# Adaptor485.net
KiCad netlist of a schematic drawn in EAGLE
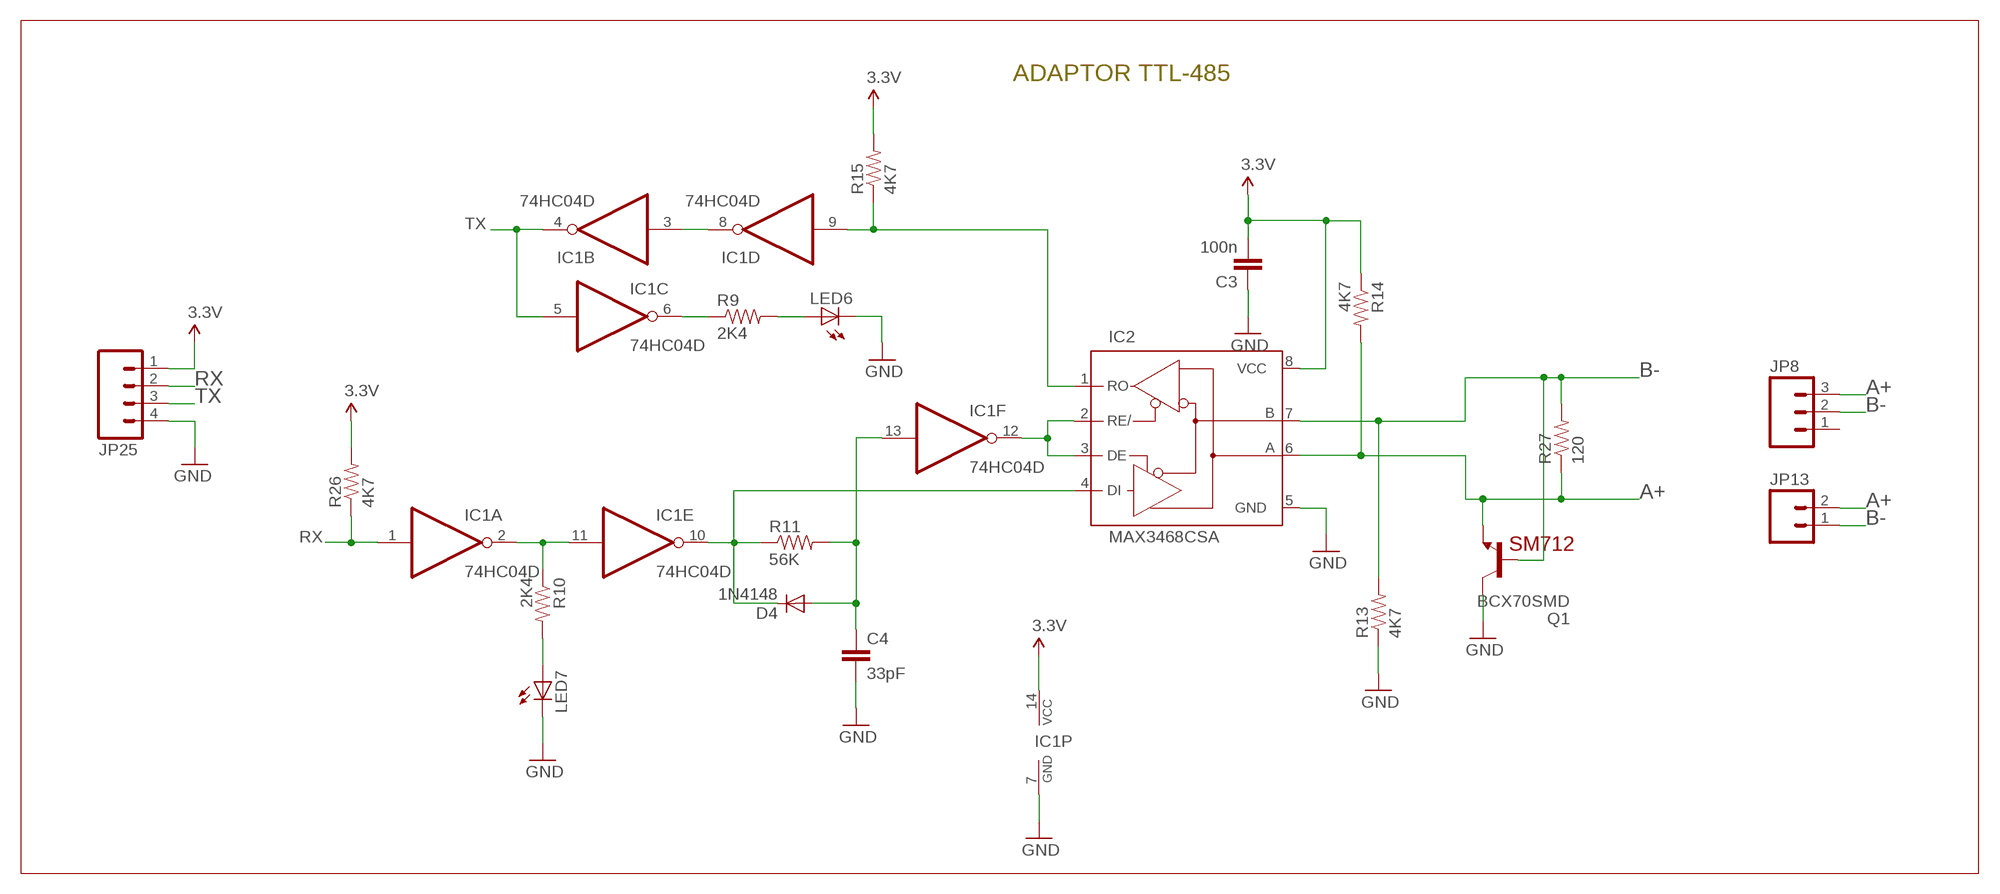
[diagram p0: schematic, sheet 1]

(export (version "E")
  (design (tool "Eeschema 10.0.6"))
  (components
    (comp (ref "C3")
      (value "100n")
      (footprint "eagle-import:0805")
      (libsource (lib "eagle-import") (part "CAP0805"))
    )
    (comp (ref "C4")
      (value "33pF")
      (footprint "eagle-import:0805")
      (libsource (lib "eagle-import") (part "CAP0805"))
    )
    (comp (ref "D4")
      (value "1N4148")
      (footprint "eagle-import:MINIMELF")
      (libsource (lib "eagle-import") (part "DIODE-MINIMELF"))
    )
    (comp (ref "IC1")
      (value "74HC04D")
      (footprint "eagle-import:SO14")
      (libsource (lib "eagle-import") (part "7404DHC"))
    )
    (comp (ref "IC2")
      (value "MAX3468CSA")
      (footprint "eagle-import:SO08")
      (fields (field (name "MPN") "MAX3468CSA+"))
      (libsource (lib "eagle-import") (part "MAX34SA68C"))
    )
    (comp (ref "JP8")
      (value "M03-SCREW-5MM")
      (footprint "eagle-import:SCREWTERMINAL-5MM-3")
      (libsource (lib "eagle-import") (part "M03-SCREW-5MM"))
    )
    (comp (ref "JP13")
      (value "M025MM")
      (footprint "eagle-import:SCREWTERMINAL-5MM-2")
      (libsource (lib "eagle-import") (part "M025MM"))
    )
    (comp (ref "JP25")
      (value "M04PTH")
      (footprint "eagle-import:1X04")
      (libsource (lib "eagle-import") (part "M04PTH"))
    )
    (comp (ref "LED6")
      (value "LEDCHIP-LED0805")
      (footprint "eagle-import:CHIP-LED0805")
      (libsource (lib "eagle-import") (part "LEDCHIP-LED0805"))
    )
    (comp (ref "LED7")
      (value "LEDCHIP-LED0805")
      (footprint "eagle-import:CHIP-LED0805")
      (libsource (lib "eagle-import") (part "LEDCHIP-LED0805"))
    )
    (comp (ref "Q1")
      (value "BCX70SMD")
      (footprint "eagle-import:SOT23")
      (libsource (lib "eagle-import") (part "BCX70SMD"))
    )
    (comp (ref "R9")
      (value "2K4")
      (footprint "eagle-import:0805")
      (libsource (lib "eagle-import") (part "RESISTOR0805-RES"))
    )
    (comp (ref "R10")
      (value "2K4")
      (footprint "eagle-import:0805")
      (libsource (lib "eagle-import") (part "RESISTOR0805-RES"))
    )
    (comp (ref "R11")
      (value "56K")
      (footprint "eagle-import:0805")
      (libsource (lib "eagle-import") (part "RESISTOR0805-RES"))
    )
    (comp (ref "R13")
      (value "4K7")
      (footprint "eagle-import:0805")
      (libsource (lib "eagle-import") (part "RESISTOR0805-RES"))
    )
    (comp (ref "R14")
      (value "4K7")
      (footprint "eagle-import:0805")
      (libsource (lib "eagle-import") (part "RESISTOR0805-RES"))
    )
    (comp (ref "R15")
      (value "4K7")
      (footprint "eagle-import:0805")
      (libsource (lib "eagle-import") (part "RESISTOR0805-RES"))
    )
    (comp (ref "R26")
      (value "4K7")
      (footprint "eagle-import:0805")
      (libsource (lib "eagle-import") (part "RESISTOR0805-RES"))
    )
    (comp (ref "R27")
      (value "120")
      (footprint "eagle-import:0805")
      (libsource (lib "eagle-import") (part "RESISTOR0805-RES"))
    )
  )
  (nets
    (net (code "1") (name "/A+") (class "Default")
      (node (ref "IC2") (pin "6") (pinfunction "A_6") (pintype "passive"))
      (node (ref "JP13") (pin "2") (pinfunction "2_2") (pintype "passive"))
      (node (ref "JP8") (pin "3") (pinfunction "3_3") (pintype "passive"))
      (node (ref "Q1") (pin "2") (pinfunction "E_2") (pintype "passive"))
      (node (ref "R14") (pin "2") (pinfunction "2_2") (pintype "passive"))
      (node (ref "R27") (pin "1") (pinfunction "1_1") (pintype "passive"))
    )
    (net (code "2") (name "/B-") (class "Default")
      (node (ref "IC2") (pin "7") (pinfunction "B_7") (pintype "passive"))
      (node (ref "JP13") (pin "1") (pinfunction "1_1") (pintype "passive"))
      (node (ref "JP8") (pin "2") (pinfunction "2_2") (pintype "passive"))
      (node (ref "Q1") (pin "1") (pinfunction "B_1") (pintype "passive"))
      (node (ref "R13") (pin "2") (pinfunction "2_2") (pintype "passive"))
      (node (ref "R27") (pin "2") (pinfunction "2_2") (pintype "passive"))
    )
    (net (code "3") (name "/RX") (class "Default")
      (node (ref "IC1") (pin "1") (pinfunction "I_1") (pintype "input"))
      (node (ref "JP25") (pin "2") (pinfunction "2_2") (pintype "passive"))
      (node (ref "R26") (pin "1") (pinfunction "1_1") (pintype "passive"))
    )
    (net (code "4") (name "/TX") (class "Default")
      (node (ref "IC1") (pin "4") (pinfunction "O_4") (pintype "output"))
      (node (ref "IC1") (pin "5") (pinfunction "I_5") (pintype "input"))
      (node (ref "JP25") (pin "3") (pinfunction "3_3") (pintype "passive"))
    )
    (net (code "5") (name "3.3V") (class "Default")
      (node (ref "C3") (pin "2") (pinfunction "2_2") (pintype "passive"))
      (node (ref "IC1") (pin "14") (pinfunction "VCC_14") (pintype "power_in"))
      (node (ref "IC2") (pin "8") (pinfunction "VCC_8") (pintype "power_in"))
      (node (ref "JP25") (pin "1") (pinfunction "1_1") (pintype "passive"))
      (node (ref "R14") (pin "1") (pinfunction "1_1") (pintype "passive"))
      (node (ref "R15") (pin "2") (pinfunction "2_2") (pintype "passive"))
      (node (ref "R26") (pin "2") (pinfunction "2_2") (pintype "passive"))
    )
    (net (code "6") (name "GND") (class "Default")
      (node (ref "C3") (pin "1") (pinfunction "1_1") (pintype "passive"))
      (node (ref "C4") (pin "2") (pinfunction "2_2") (pintype "passive"))
      (node (ref "IC1") (pin "7") (pinfunction "GND_7") (pintype "power_in"))
      (node (ref "IC2") (pin "5") (pinfunction "GND_5") (pintype "power_in"))
      (node (ref "JP25") (pin "4") (pinfunction "4_4") (pintype "passive"))
      (node (ref "LED6") (pin "C") (pinfunction "C_C") (pintype "passive"))
      (node (ref "LED7") (pin "C") (pinfunction "C_C") (pintype "passive"))
      (node (ref "Q1") (pin "3") (pinfunction "C_3") (pintype "passive"))
      (node (ref "R13") (pin "1") (pinfunction "1_1") (pintype "passive"))
    )
    (net (code "7") (name "Net-(IC1A-O)") (class "Default")
      (node (ref "IC1") (pin "11") (pinfunction "I_11") (pintype "input"))
      (node (ref "IC1") (pin "2") (pinfunction "O_2") (pintype "output"))
      (node (ref "R10") (pin "1") (pinfunction "1_1") (pintype "passive"))
    )
    (net (code "8") (name "Net-(IC1B-I)") (class "Default")
      (node (ref "IC1") (pin "3") (pinfunction "I_3") (pintype "input"))
      (node (ref "IC1") (pin "8") (pinfunction "O_8") (pintype "output"))
    )
    (net (code "9") (name "Net-(IC1C-O)") (class "Default")
      (node (ref "IC1") (pin "6") (pinfunction "O_6") (pintype "output"))
      (node (ref "R9") (pin "1") (pinfunction "1_1") (pintype "passive"))
    )
    (net (code "10") (name "Net-(IC1D-I)") (class "Default")
      (node (ref "IC1") (pin "9") (pinfunction "I_9") (pintype "input"))
      (node (ref "IC2") (pin "1") (pinfunction "RO_1") (pintype "output"))
      (node (ref "R15") (pin "1") (pinfunction "1_1") (pintype "passive"))
    )
    (net (code "11") (name "Net-(IC1E-O)") (class "Default")
      (node (ref "D4") (pin "C") (pinfunction "C_C") (pintype "passive"))
      (node (ref "IC1") (pin "10") (pinfunction "O_10") (pintype "output"))
      (node (ref "IC2") (pin "4") (pinfunction "DI_4") (pintype "input"))
      (node (ref "R11") (pin "1") (pinfunction "1_1") (pintype "passive"))
    )
    (net (code "12") (name "Net-(IC1F-I)") (class "Default")
      (node (ref "C4") (pin "1") (pinfunction "1_1") (pintype "passive"))
      (node (ref "D4") (pin "A") (pinfunction "A_A") (pintype "passive"))
      (node (ref "IC1") (pin "13") (pinfunction "I_13") (pintype "input"))
      (node (ref "R11") (pin "2") (pinfunction "2_2") (pintype "passive"))
    )
    (net (code "13") (name "Net-(IC1F-O)") (class "Default")
      (node (ref "IC1") (pin "12") (pinfunction "O_12") (pintype "output"))
      (node (ref "IC2") (pin "2") (pinfunction "RE/_2") (pintype "input"))
      (node (ref "IC2") (pin "3") (pinfunction "DE_3") (pintype "input"))
    )
    (net (code "14") (name "Net-(LED6-PadA)") (class "Default")
      (node (ref "LED6") (pin "A") (pinfunction "A_A") (pintype "passive"))
      (node (ref "R9") (pin "2") (pinfunction "2_2") (pintype "passive"))
    )
    (net (code "15") (name "Net-(LED7-PadA)") (class "Default")
      (node (ref "LED7") (pin "A") (pinfunction "A_A") (pintype "passive"))
      (node (ref "R10") (pin "2") (pinfunction "2_2") (pintype "passive"))
    )
    (net (code "16") (name "unconnected-(JP8-Pad1)") (class "Default")
      (node (ref "JP8") (pin "1") (pinfunction "1_1") (pintype "passive"))
    )
  )
)
